# MCU.net
KiCad netlist of a schematic drawn in Altium Designer
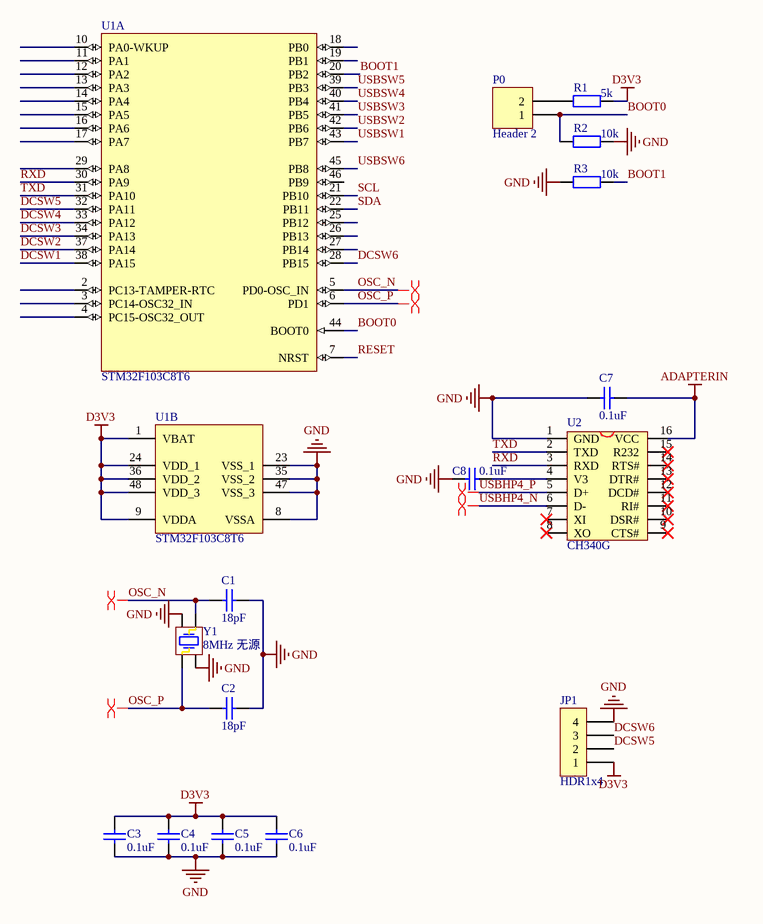
[diagram p0: MCU.SchDoc]

(export (version "E")
  (design (tool "Eeschema 10.0.6"))
  (components
    (comp (ref "C1")
      (value "18pF")
      (footprint "0603C")
      (description "Capacitor")
      (fields (field (name "PUBLISHER") "Altium Limited"))
      (libsource (lib "Crazy_PCB") (part "Cap"))
    )
    (comp (ref "C2")
      (value "18pF")
      (footprint "0603C")
      (description "Capacitor")
      (fields (field (name "PUBLISHER") "Altium Limited"))
      (libsource (lib "Crazy_PCB") (part "Cap"))
    )
    (comp (ref "C3")
      (value "0.1uF")
      (footprint "0603C")
      (description "Capacitor")
      (fields (field (name "PUBLISHER") "Altium Limited"))
      (libsource (lib "Crazy_PCB") (part "Cap"))
    )
    (comp (ref "C4")
      (value "0.1uF")
      (footprint "0603C")
      (description "Capacitor")
      (fields (field (name "PUBLISHER") "Altium Limited"))
      (libsource (lib "Crazy_PCB") (part "Cap"))
    )
    (comp (ref "C5")
      (value "0.1uF")
      (footprint "0603C")
      (description "Capacitor")
      (fields (field (name "PUBLISHER") "Altium Limited"))
      (libsource (lib "Crazy_PCB") (part "Cap"))
    )
    (comp (ref "C6")
      (value "0.1uF")
      (footprint "0603C")
      (description "Capacitor")
      (fields (field (name "PUBLISHER") "Altium Limited"))
      (libsource (lib "Crazy_PCB") (part "Cap"))
    )
    (comp (ref "C7")
      (value "0.1uF")
      (footprint "0603C")
      (description "Capacitor")
      (fields (field (name "PUBLISHER") "Altium Limited"))
      (libsource (lib "Crazy_PCB") (part "Cap"))
    )
    (comp (ref "C8")
      (value "0.1uF")
      (footprint "0603C")
      (description "Capacitor")
      (fields (field (name "PUBLISHER") "Altium Limited"))
      (libsource (lib "Crazy_PCB") (part "Cap"))
    )
    (comp (ref "JP1")
      (value "HDR1x4")
      (footprint "XH-4-SIDE")
      (description "Connector")
      (libsource (lib "General") (part "HDR1x4"))
    )
    (comp (ref "P0")
      (value "Header 2")
      (footprint "HDR1X2")
      (description "Header, 2-Pin")
      (fields (field (name "PUBLISHER") "Altium Limited"))
      (libsource (lib "Miscellaneous Connectors") (part "Header 2"))
    )
    (comp (ref "R1")
      (value "5k")
      (footprint "0603R")
      (description "Resistor")
      (fields (field (name "PUBLISHER") "Altium Limited"))
      (libsource (lib "Crazy_PCB") (part "RES"))
    )
    (comp (ref "R2")
      (value "10k")
      (footprint "0603R")
      (description "Resistor")
      (fields (field (name "PUBLISHER") "Altium Limited"))
      (libsource (lib "") (part "RES_1"))
    )
    (comp (ref "R3")
      (value "10k")
      (footprint "0603R")
      (description "Resistor")
      (fields (field (name "PUBLISHER") "Altium Limited"))
      (libsource (lib "Crazy_PCB") (part "RES"))
    )
    (comp (ref "U1")
      (value "STM32F103C8T6")
      (footprint "LQFP48_N")
      (libsource (lib "STMicroelectronics STM32 F1") (part "STM32F103C8T6"))
    )
    (comp (ref "U2")
      (value "CH340G")
      (footprint "SOP-16")
      (description "USB2UART")
      (libsource (lib "WarShip V3 STM32103封装库") (part "CH340G"))
    )
    (comp (ref "Y1")
      (value "8MHz 无源")
      (footprint "X3225")
      (description "Crystal Oscillator")
      (fields (field (name "PUBLISHER") "Altium Limited"))
      (libsource (lib "JL_SCH") (part "XTAL_1"))
    )
  )
  (nets
    (net (code "1") (name "/BOOT0") (class "Default")
      (node (ref "P0") (pin "1") (pinfunction "1_1") (pintype "passive"))
      (node (ref "R2") (pin "1") (pinfunction "1_1") (pintype "passive"))
      (node (ref "U1") (pin "44") (pinfunction "BOOT0_44") (pintype "input"))
    )
    (net (code "2") (name "/BOOT1") (class "Default")
      (node (ref "R3") (pin "1") (pinfunction "1_1") (pintype "passive"))
      (node (ref "U1") (pin "20") (pinfunction "PB2_20") (pintype "bidirectional"))
    )
    (net (code "3") (name "/DCSW1") (class "Default")
      (node (ref "U1") (pin "38") (pinfunction "PA15_38") (pintype "bidirectional"))
    )
    (net (code "4") (name "/DCSW2") (class "Default")
      (node (ref "U1") (pin "37") (pinfunction "PA14_37") (pintype "bidirectional"))
    )
    (net (code "5") (name "/DCSW3") (class "Default")
      (node (ref "U1") (pin "34") (pinfunction "PA13_34") (pintype "bidirectional"))
    )
    (net (code "6") (name "/DCSW4") (class "Default")
      (node (ref "U1") (pin "33") (pinfunction "PA12_33") (pintype "bidirectional"))
    )
    (net (code "7") (name "/DCSW5") (class "Default")
      (node (ref "JP1") (pin "2") (pinfunction "2_2") (pintype "passive"))
      (node (ref "U1") (pin "32") (pinfunction "PA11_32") (pintype "bidirectional"))
    )
    (net (code "8") (name "/DCSW6") (class "Default")
      (node (ref "JP1") (pin "3") (pinfunction "3_3") (pintype "passive"))
      (node (ref "U1") (pin "28") (pinfunction "PB15_28") (pintype "bidirectional"))
    )
    (net (code "9") (name "/OSC_N") (class "Default")
      (node (ref "C1") (pin "1") (pinfunction "1_1") (pintype "passive"))
      (node (ref "U1") (pin "5") (pinfunction "PD0-OSC_IN_5") (pintype "bidirectional"))
      (node (ref "Y1") (pin "3") (pinfunction "OSC2_3") (pintype "passive"))
    )
    (net (code "10") (name "/OSC_P") (class "Default")
      (node (ref "C2") (pin "1") (pinfunction "1_1") (pintype "passive"))
      (node (ref "U1") (pin "6") (pinfunction "PD1_6") (pintype "bidirectional"))
      (node (ref "Y1") (pin "1") (pinfunction "OSC1_1") (pintype "passive"))
    )
    (net (code "11") (name "/RESET") (class "Default")
      (node (ref "U1") (pin "7") (pinfunction "NRST_7") (pintype "bidirectional"))
    )
    (net (code "12") (name "/RXD") (class "Default")
      (node (ref "U1") (pin "30") (pinfunction "PA9_30") (pintype "bidirectional"))
      (node (ref "U2") (pin "3") (pinfunction "RXD_3") (pintype "passive"))
    )
    (net (code "13") (name "/SCL") (class "Default")
      (node (ref "U1") (pin "21") (pinfunction "PB10_21") (pintype "bidirectional"))
    )
    (net (code "14") (name "/SDA") (class "Default")
      (node (ref "U1") (pin "22") (pinfunction "PB11_22") (pintype "bidirectional"))
    )
    (net (code "15") (name "/TXD") (class "Default")
      (node (ref "U1") (pin "31") (pinfunction "PA10_31") (pintype "bidirectional"))
      (node (ref "U2") (pin "2") (pinfunction "TXD_2") (pintype "passive"))
    )
    (net (code "16") (name "/USBHP4_N") (class "Default")
      (node (ref "U2") (pin "6") (pinfunction "D-_6") (pintype "passive"))
    )
    (net (code "17") (name "/USBHP4_P") (class "Default")
      (node (ref "U2") (pin "5") (pinfunction "D+_5") (pintype "passive"))
    )
    (net (code "18") (name "/USBSW1") (class "Default")
      (node (ref "U1") (pin "43") (pinfunction "PB7_43") (pintype "bidirectional"))
    )
    (net (code "19") (name "/USBSW2") (class "Default")
      (node (ref "U1") (pin "42") (pinfunction "PB6_42") (pintype "bidirectional"))
    )
    (net (code "20") (name "/USBSW3") (class "Default")
      (node (ref "U1") (pin "41") (pinfunction "PB5_41") (pintype "bidirectional"))
    )
    (net (code "21") (name "/USBSW4") (class "Default")
      (node (ref "U1") (pin "40") (pinfunction "PB4_40") (pintype "bidirectional"))
    )
    (net (code "22") (name "/USBSW5") (class "Default")
      (node (ref "U1") (pin "39") (pinfunction "PB3_39") (pintype "bidirectional"))
    )
    (net (code "23") (name "/USBSW6") (class "Default")
      (node (ref "U1") (pin "45") (pinfunction "PB8_45") (pintype "bidirectional"))
    )
    (net (code "24") (name "ADAPTERIN") (class "Default")
      (node (ref "C7") (pin "2") (pinfunction "2_2") (pintype "passive"))
      (node (ref "U2") (pin "16") (pinfunction "VCC_16") (pintype "passive"))
    )
    (net (code "25") (name "D3V3") (class "Default")
      (node (ref "C3") (pin "1") (pinfunction "1_1") (pintype "passive"))
      (node (ref "C4") (pin "1") (pinfunction "1_1") (pintype "passive"))
      (node (ref "C5") (pin "1") (pinfunction "1_1") (pintype "passive"))
      (node (ref "C6") (pin "1") (pinfunction "1_1") (pintype "passive"))
      (node (ref "JP1") (pin "1") (pinfunction "1_1") (pintype "passive"))
      (node (ref "R1") (pin "1") (pinfunction "1_1") (pintype "passive"))
      (node (ref "U1") (pin "1") (pinfunction "VBAT_1") (pintype "power_in"))
      (node (ref "U1") (pin "24") (pinfunction "VDD_1_24") (pintype "power_in"))
      (node (ref "U1") (pin "36") (pinfunction "VDD_2_36") (pintype "power_in"))
      (node (ref "U1") (pin "48") (pinfunction "VDD_3_48") (pintype "power_in"))
      (node (ref "U1") (pin "9") (pinfunction "VDDA_9") (pintype "power_in"))
    )
    (net (code "26") (name "GND") (class "Default")
      (node (ref "C1") (pin "2") (pinfunction "2_2") (pintype "passive"))
      (node (ref "C2") (pin "2") (pinfunction "2_2") (pintype "passive"))
      (node (ref "C3") (pin "2") (pinfunction "2_2") (pintype "passive"))
      (node (ref "C4") (pin "2") (pinfunction "2_2") (pintype "passive"))
      (node (ref "C5") (pin "2") (pinfunction "2_2") (pintype "passive"))
      (node (ref "C6") (pin "2") (pinfunction "2_2") (pintype "passive"))
      (node (ref "C7") (pin "1") (pinfunction "1_1") (pintype "passive"))
      (node (ref "C8") (pin "1") (pinfunction "1_1") (pintype "passive"))
      (node (ref "JP1") (pin "4") (pinfunction "4_4") (pintype "passive"))
      (node (ref "R2") (pin "2") (pinfunction "2_2") (pintype "passive"))
      (node (ref "R3") (pin "2") (pinfunction "2_2") (pintype "passive"))
      (node (ref "U1") (pin "23") (pinfunction "VSS_1_23") (pintype "power_in"))
      (node (ref "U1") (pin "35") (pinfunction "VSS_2_35") (pintype "power_in"))
      (node (ref "U1") (pin "47") (pinfunction "VSS_3_47") (pintype "power_in"))
      (node (ref "U1") (pin "8") (pinfunction "VSSA_8") (pintype "power_in"))
      (node (ref "U2") (pin "1") (pinfunction "GND_1") (pintype "passive"))
      (node (ref "Y1") (pin "2") (pinfunction "NA_2") (pintype "passive"))
      (node (ref "Y1") (pin "4") (pinfunction "NA_4") (pintype "passive"))
    )
    (net (code "27") (name "Net-(P0-Pad2)") (class "Default")
      (node (ref "P0") (pin "2") (pinfunction "2_2") (pintype "passive"))
      (node (ref "R1") (pin "2") (pinfunction "2_2") (pintype "passive"))
    )
    (net (code "28") (name "Net-(U2-V3)") (class "Default")
      (node (ref "C8") (pin "2") (pinfunction "2_2") (pintype "passive"))
      (node (ref "U2") (pin "4") (pinfunction "V3_4") (pintype "passive"))
    )
    (net (code "29") (name "unconnected-(U1A-PA0-WKUP-Pad10)") (class "Default")
      (node (ref "U1") (pin "10") (pinfunction "PA0-WKUP_10") (pintype "bidirectional"))
    )
    (net (code "30") (name "unconnected-(U1A-PA1-Pad11)") (class "Default")
      (node (ref "U1") (pin "11") (pinfunction "PA1_11") (pintype "bidirectional"))
    )
    (net (code "31") (name "unconnected-(U1A-PA2-Pad12)") (class "Default")
      (node (ref "U1") (pin "12") (pinfunction "PA2_12") (pintype "bidirectional"))
    )
    (net (code "32") (name "unconnected-(U1A-PA3-Pad13)") (class "Default")
      (node (ref "U1") (pin "13") (pinfunction "PA3_13") (pintype "bidirectional"))
    )
    (net (code "33") (name "unconnected-(U1A-PA4-Pad14)") (class "Default")
      (node (ref "U1") (pin "14") (pinfunction "PA4_14") (pintype "bidirectional"))
    )
    (net (code "34") (name "unconnected-(U1A-PA5-Pad15)") (class "Default")
      (node (ref "U1") (pin "15") (pinfunction "PA5_15") (pintype "bidirectional"))
    )
    (net (code "35") (name "unconnected-(U1A-PA6-Pad16)") (class "Default")
      (node (ref "U1") (pin "16") (pinfunction "PA6_16") (pintype "bidirectional"))
    )
    (net (code "36") (name "unconnected-(U1A-PA7-Pad17)") (class "Default")
      (node (ref "U1") (pin "17") (pinfunction "PA7_17") (pintype "bidirectional"))
    )
    (net (code "37") (name "unconnected-(U1A-PA8-Pad29)") (class "Default")
      (node (ref "U1") (pin "29") (pinfunction "PA8_29") (pintype "bidirectional"))
    )
    (net (code "38") (name "unconnected-(U1A-PB0-Pad18)") (class "Default")
      (node (ref "U1") (pin "18") (pinfunction "PB0_18") (pintype "bidirectional"))
    )
    (net (code "39") (name "unconnected-(U1A-PB1-Pad19)") (class "Default")
      (node (ref "U1") (pin "19") (pinfunction "PB1_19") (pintype "bidirectional"))
    )
    (net (code "40") (name "unconnected-(U1A-PB9-Pad46)") (class "Default")
      (node (ref "U1") (pin "46") (pinfunction "PB9_46") (pintype "bidirectional"))
    )
    (net (code "41") (name "unconnected-(U1A-PB12-Pad25)") (class "Default")
      (node (ref "U1") (pin "25") (pinfunction "PB12_25") (pintype "bidirectional"))
    )
    (net (code "42") (name "unconnected-(U1A-PB13-Pad26)") (class "Default")
      (node (ref "U1") (pin "26") (pinfunction "PB13_26") (pintype "bidirectional"))
    )
    (net (code "43") (name "unconnected-(U1A-PB14-Pad27)") (class "Default")
      (node (ref "U1") (pin "27") (pinfunction "PB14_27") (pintype "bidirectional"))
    )
    (net (code "44") (name "unconnected-(U1A-PC13-TAMPER-RTC-Pad2)") (class "Default")
      (node (ref "U1") (pin "2") (pinfunction "PC13-TAMPER-RTC_2") (pintype "bidirectional"))
    )
    (net (code "45") (name "unconnected-(U1A-PC14-OSC32_IN-Pad3)") (class "Default")
      (node (ref "U1") (pin "3") (pinfunction "PC14-OSC32_IN_3") (pintype "bidirectional"))
    )
    (net (code "46") (name "unconnected-(U1A-PC15-OSC32_OUT-Pad4)") (class "Default")
      (node (ref "U1") (pin "4") (pinfunction "PC15-OSC32_OUT_4") (pintype "bidirectional"))
    )
    (net (code "47") (name "unconnected-(U2-CTS#-Pad9)") (class "Default")
      (node (ref "U2") (pin "9") (pinfunction "CTS#_9") (pintype "passive+no_connect"))
    )
    (net (code "48") (name "unconnected-(U2-DCD#-Pad12)") (class "Default")
      (node (ref "U2") (pin "12") (pinfunction "DCD#_12") (pintype "passive+no_connect"))
    )
    (net (code "49") (name "unconnected-(U2-DSR#-Pad10)") (class "Default")
      (node (ref "U2") (pin "10") (pinfunction "DSR#_10") (pintype "passive+no_connect"))
    )
    (net (code "50") (name "unconnected-(U2-DTR#-Pad13)") (class "Default")
      (node (ref "U2") (pin "13") (pinfunction "DTR#_13") (pintype "passive+no_connect"))
    )
    (net (code "51") (name "unconnected-(U2-R232-Pad15)") (class "Default")
      (node (ref "U2") (pin "15") (pinfunction "R232_15") (pintype "passive+no_connect"))
    )
    (net (code "52") (name "unconnected-(U2-RI#-Pad11)") (class "Default")
      (node (ref "U2") (pin "11") (pinfunction "RI#_11") (pintype "passive+no_connect"))
    )
    (net (code "53") (name "unconnected-(U2-RTS#-Pad14)") (class "Default")
      (node (ref "U2") (pin "14") (pinfunction "RTS#_14") (pintype "passive+no_connect"))
    )
    (net (code "54") (name "unconnected-(U2-XI-Pad7)") (class "Default")
      (node (ref "U2") (pin "7") (pinfunction "XI_7") (pintype "passive+no_connect"))
    )
    (net (code "55") (name "unconnected-(U2-XO-Pad8)") (class "Default")
      (node (ref "U2") (pin "8") (pinfunction "XO_8") (pintype "passive+no_connect"))
    )
  )
)
